# USB_Type_C.net
KiCad netlist of a schematic drawn in Altium Designer
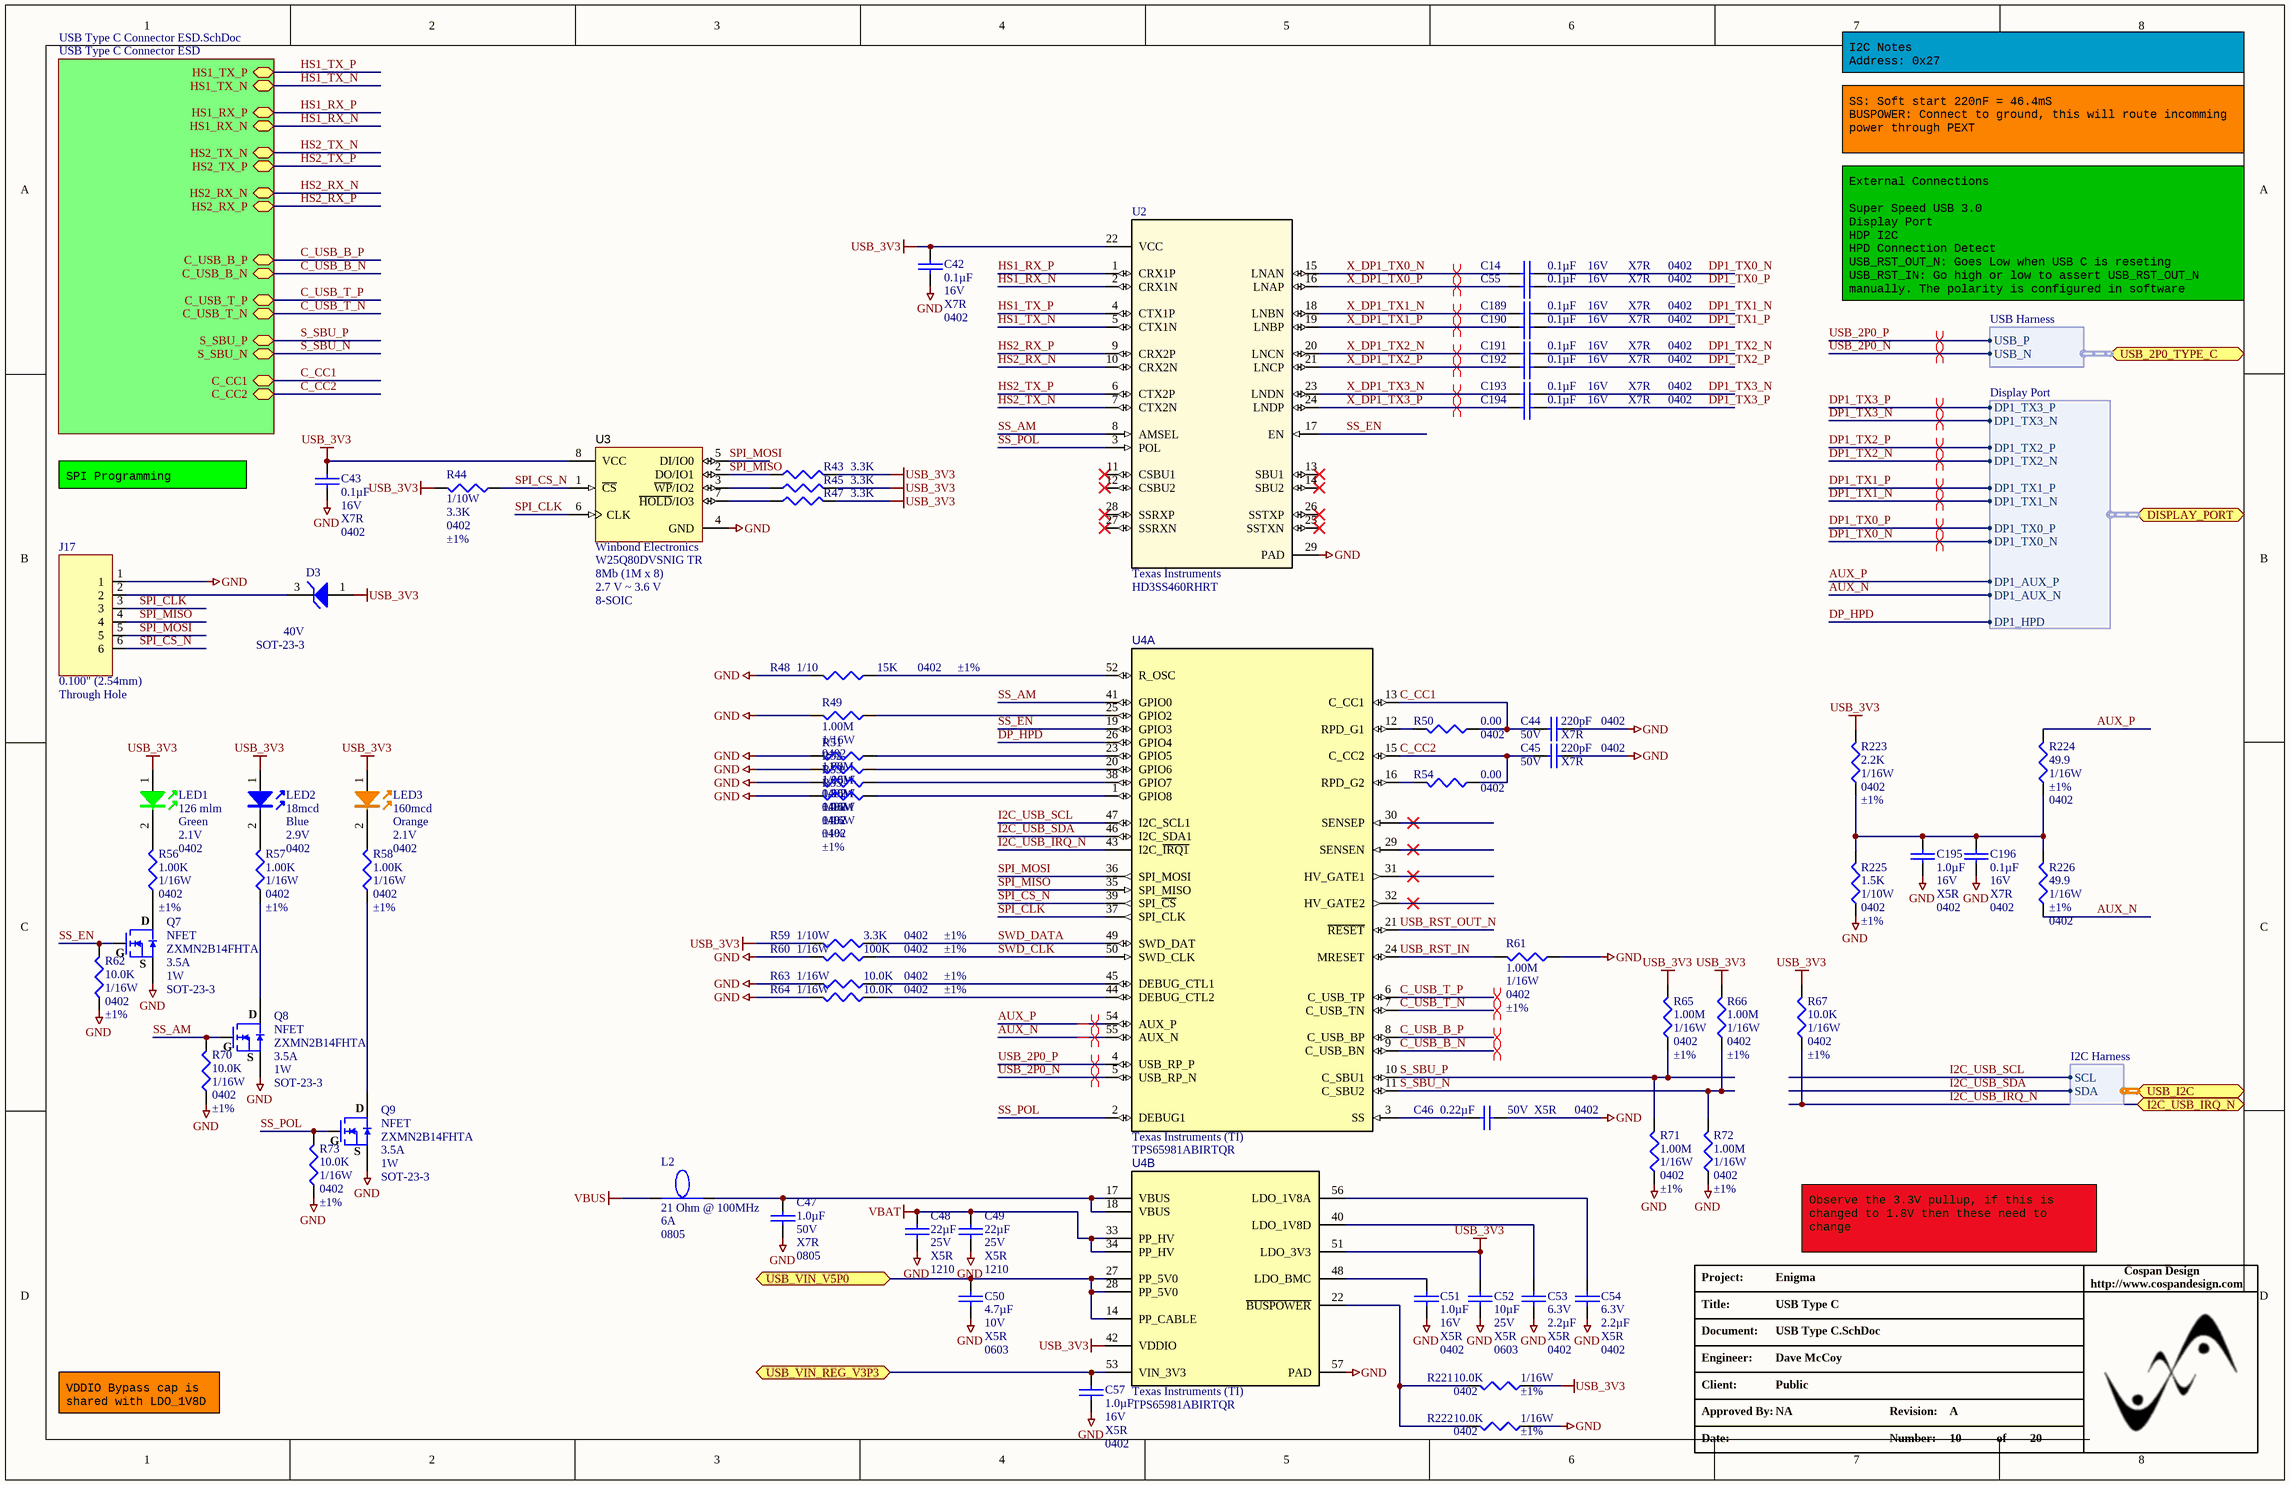
[diagram p0: USB Type C.SchDoc]

(export (version "E")
  (design (tool "Eeschema 10.0.6"))
  (components
    (comp (ref "C14")
      (value "0.1uF")
      (footprint "C_0402")
      (description "CAP CER .10UF 16V X7R 0402")
      (fields
        (field (name "MANUFACTURER") "Murata Electronics North America")
        (field (name "MANUFACTURER PART NUMBER") "GRM155R71C104KA88J")
        (field (name "CAPACITANCE") "0.1µF")
        (field (name "VOLTAGE - RATED") "16V")
        (field (name "TEMPERATURE COEFFICIENT") "X7R")
        (field (name "PACKAGE / CASE") "0402")
      )
      (libsource (lib "Main LibraryX") (part "C_0402_0.1UF_16V"))
    )
    (comp (ref "C42")
      (value "0.1uF")
      (footprint "C_0402")
      (description "CAP CER .10UF 16V X7R 0402")
      (fields
        (field (name "MANUFACTURER") "Murata Electronics North America")
        (field (name "MANUFACTURER PART NUMBER") "GRM155R71C104KA88J")
        (field (name "CAPACITANCE") "0.1µF")
        (field (name "VOLTAGE - RATED") "16V")
        (field (name "TEMPERATURE COEFFICIENT") "X7R")
        (field (name "PACKAGE / CASE") "0402")
      )
      (libsource (lib "Main LibraryX") (part "C_0402_0.1UF_16V"))
    )
    (comp (ref "C43")
      (value "0.1uF")
      (footprint "C_0402")
      (description "CAP CER .10UF 16V X7R 0402")
      (fields
        (field (name "MANUFACTURER") "Murata Electronics North America")
        (field (name "MANUFACTURER PART NUMBER") "GRM155R71C104KA88J")
        (field (name "CAPACITANCE") "0.1µF")
        (field (name "VOLTAGE - RATED") "16V")
        (field (name "TEMPERATURE COEFFICIENT") "X7R")
        (field (name "PACKAGE / CASE") "0402")
      )
      (libsource (lib "Main LibraryX") (part "C_0402_0.1UF_16V"))
    )
    (comp (ref "C44")
      (value "220pF")
      (footprint "C_0402")
      (description "CAP CER 220PF 50V 10% X7R 0402")
      (fields
        (field (name "MANUFACTURER") "Murata Electronics North America")
        (field (name "MANUFACTURER PART NUMBER") "GRM155R71H221KA01D")
        (field (name "CAPACITANCE") "220pF")
        (field (name "VOLTAGE - RATED") "50V")
        (field (name "TEMPERATURE COEFFICIENT") "X7R")
        (field (name "PACKAGE / CASE") "0402")
      )
      (libsource (lib "Main Library") (part "C_0402_220PF_50V"))
    )
    (comp (ref "C45")
      (value "220pF")
      (footprint "C_0402")
      (description "CAP CER 220PF 50V 10% X7R 0402")
      (fields
        (field (name "MANUFACTURER") "Murata Electronics North America")
        (field (name "MANUFACTURER PART NUMBER") "GRM155R71H221KA01D")
        (field (name "CAPACITANCE") "220pF")
        (field (name "VOLTAGE - RATED") "50V")
        (field (name "TEMPERATURE COEFFICIENT") "X7R")
        (field (name "PACKAGE / CASE") "0402")
      )
      (libsource (lib "Main Library") (part "C_0402_220PF_50V"))
    )
    (comp (ref "C46")
      (value "C_0402_0.22UF_50V")
      (footprint "C_0402")
      (description "CAP CER 0.22UF 50V X5R 0402")
      (fields
        (field (name "MANUFACTURER") "Taiyo Yuden")
        (field (name "MANUFACTURER PART NUMBER") "UMK105BJ224KV-F")
        (field (name "CAPACITANCE") "0.22µF")
        (field (name "VOLTAGE - RATED") "50V")
        (field (name "TEMPERATURE COEFFICIENT") "X5R")
        (field (name "PACKAGE / CASE") "0402")
      )
      (libsource (lib "Main Library") (part "C_0402_0.22UF_50V"))
    )
    (comp (ref "C47")
      (value "1.0uF")
      (footprint "C_ERA-0805")
      (description "CAP CER 1UF 50V X7R 0805")
      (fields
        (field (name "MANUFACTURER") "Murata Electronics North America")
        (field (name "MANUFACTURER PART NUMBER") "GRM21BR71H105KA12L")
        (field (name "CAPACITANCE") "1.0µF")
        (field (name "VOLTAGE - RATED") "50V")
        (field (name "TEMPERATURE COEFFICIENT") "X7R")
        (field (name "PACKAGE / CASE") "0805")
      )
      (libsource (lib "Main Library") (part "C_0805_1.0uF_50V"))
    )
    (comp (ref "C48")
      (value "22µF")
      (footprint "C_14-1210")
      (description "CAP CER 22UF 25V 20% X5R 1210")
      (fields
        (field (name "MANUFACTURER") "Taiyo Yuden")
        (field (name "MANUFACTURER PART NUMBER") "TMK325BJ226MM-T")
        (field (name "CAPACITANCE") "22µF")
        (field (name "VOLTAGE - RATED") "25V")
        (field (name "TEMPERATURE COEFFICIENT") "X5R")
        (field (name "PACKAGE / CASE") "1210")
      )
      (libsource (lib "Main Library") (part "C_1210_22µF"))
    )
    (comp (ref "C49")
      (value "22µF")
      (footprint "C_14-1210")
      (description "CAP CER 22UF 25V 20% X5R 1210")
      (fields
        (field (name "MANUFACTURER") "Taiyo Yuden")
        (field (name "MANUFACTURER PART NUMBER") "TMK325BJ226MM-T")
        (field (name "CAPACITANCE") "22µF")
        (field (name "VOLTAGE - RATED") "25V")
        (field (name "TEMPERATURE COEFFICIENT") "X5R")
        (field (name "PACKAGE / CASE") "1210")
      )
      (libsource (lib "Main Library") (part "C_1210_22µF"))
    )
    (comp (ref "C50")
      (value "4.7µF")
      (footprint "C_ERA-0603")
      (description "CAP CER 4.7UF 10V X5R 0603")
      (fields
        (field (name "MANUFACTURER") "Murata Electronics North America")
        (field (name "MANUFACTURER PART NUMBER") "GRM188R61A475KE15D")
        (field (name "CAPACITANCE") "4.7µF")
        (field (name "VOLTAGE - RATED") "10V")
        (field (name "TEMPERATURE COEFFICIENT") "X5R")
        (field (name "PACKAGE / CASE") "0603")
      )
      (libsource (lib "Main LibraryX") (part "C_0603_4.7uF_10V"))
    )
    (comp (ref "C51")
      (value "1.0uF")
      (footprint "C_ERA-0402")
      (description "CAP CER 1.0UF 16V X5R 0402")
      (fields
        (field (name "MANUFACTURER") "Taiyo Yuden")
        (field (name "MANUFACTURER PART NUMBER") "EMK105BJ105KV-F")
        (field (name "CAPACITANCE") "1.0µF")
        (field (name "VOLTAGE - RATED") "16V")
        (field (name "TEMPERATURE COEFFICIENT") "X5R")
        (field (name "PACKAGE / CASE") "0402")
      )
      (libsource (lib "Main LibraryX") (part "C_0402_1.0UF_16V"))
    )
    (comp (ref "C52")
      (value "C_0603_10µF")
      (footprint "C_ERA-0603")
      (description "CAP CER 10UF 16V X5R 0603")
      (fields
        (field (name "MANUFACTURER") "Murata Electronics North America")
        (field (name "MANUFACTURER PART NUMBER") "GRM188R61C106MA73D")
        (field (name "CAPACITANCE") "10µF")
        (field (name "VOLTAGE - RATED") "25V")
        (field (name "TEMPERATURE COEFFICIENT") "X5R")
        (field (name "PACKAGE / CASE") "0603")
      )
      (libsource (lib "Cospan Design") (part "C_0603_10µF"))
    )
    (comp (ref "C53")
      (value "2.2uF")
      (footprint "C_0402")
      (description "CAP CER 2.2UF 6.3V X5R 0402")
      (fields
        (field (name "MANUFACTURER") "TDK Corporation")
        (field (name "MANUFACTURER PART NUMBER") "C1005X5R0J225M")
        (field (name "VOLTAGE - RATED") "6.3V")
        (field (name "CAPACITANCE") "2.2µF")
        (field (name "TEMPERATURE COEFFICIENT") "X5R")
        (field (name "PACKAGE / CASE") "0402")
      )
      (libsource (lib "Main Library") (part "C_0402_2.2UF"))
    )
    (comp (ref "C54")
      (value "2.2uF")
      (footprint "C_0402")
      (description "CAP CER 2.2UF 6.3V X5R 0402")
      (fields
        (field (name "MANUFACTURER") "TDK Corporation")
        (field (name "MANUFACTURER PART NUMBER") "C1005X5R0J225M")
        (field (name "VOLTAGE - RATED") "6.3V")
        (field (name "CAPACITANCE") "2.2µF")
        (field (name "TEMPERATURE COEFFICIENT") "X5R")
        (field (name "PACKAGE / CASE") "0402")
      )
      (libsource (lib "Main Library") (part "C_0402_2.2UF"))
    )
    (comp (ref "C55")
      (value "0.1uF")
      (footprint "C_0402")
      (description "CAP CER .10UF 16V X7R 0402")
      (fields
        (field (name "MANUFACTURER") "Murata Electronics North America")
        (field (name "MANUFACTURER PART NUMBER") "GRM155R71C104KA88J")
        (field (name "CAPACITANCE") "0.1µF")
        (field (name "VOLTAGE - RATED") "16V")
        (field (name "TEMPERATURE COEFFICIENT") "X7R")
        (field (name "PACKAGE / CASE") "0402")
      )
      (libsource (lib "Main LibraryX") (part "C_0402_0.1UF_16V"))
    )
    (comp (ref "C57")
      (value "1.0uF")
      (footprint "C_ERA-0402")
      (description "CAP CER 1.0UF 16V X5R 0402")
      (fields
        (field (name "MANUFACTURER") "Taiyo Yuden")
        (field (name "MANUFACTURER PART NUMBER") "EMK105BJ105KV-F")
        (field (name "CAPACITANCE") "1.0µF")
        (field (name "VOLTAGE - RATED") "16V")
        (field (name "TEMPERATURE COEFFICIENT") "X5R")
        (field (name "PACKAGE / CASE") "0402")
      )
      (libsource (lib "Main LibraryX") (part "C_0402_1.0UF_16V"))
    )
    (comp (ref "C189")
      (value "0.1uF")
      (footprint "C_0402")
      (description "CAP CER .10UF 16V X7R 0402")
      (fields
        (field (name "MANUFACTURER") "Murata Electronics North America")
        (field (name "MANUFACTURER PART NUMBER") "GRM155R71C104KA88J")
        (field (name "CAPACITANCE") "0.1µF")
        (field (name "VOLTAGE - RATED") "16V")
        (field (name "TEMPERATURE COEFFICIENT") "X7R")
        (field (name "PACKAGE / CASE") "0402")
      )
      (libsource (lib "Main LibraryX") (part "C_0402_0.1UF_16V"))
    )
    (comp (ref "C190")
      (value "0.1uF")
      (footprint "C_0402")
      (description "CAP CER .10UF 16V X7R 0402")
      (fields
        (field (name "MANUFACTURER") "Murata Electronics North America")
        (field (name "MANUFACTURER PART NUMBER") "GRM155R71C104KA88J")
        (field (name "CAPACITANCE") "0.1µF")
        (field (name "VOLTAGE - RATED") "16V")
        (field (name "TEMPERATURE COEFFICIENT") "X7R")
        (field (name "PACKAGE / CASE") "0402")
      )
      (libsource (lib "Main LibraryX") (part "C_0402_0.1UF_16V"))
    )
    (comp (ref "C191")
      (value "0.1uF")
      (footprint "C_0402")
      (description "CAP CER .10UF 16V X7R 0402")
      (fields
        (field (name "MANUFACTURER") "Murata Electronics North America")
        (field (name "MANUFACTURER PART NUMBER") "GRM155R71C104KA88J")
        (field (name "CAPACITANCE") "0.1µF")
        (field (name "VOLTAGE - RATED") "16V")
        (field (name "TEMPERATURE COEFFICIENT") "X7R")
        (field (name "PACKAGE / CASE") "0402")
      )
      (libsource (lib "Main LibraryX") (part "C_0402_0.1UF_16V"))
    )
    (comp (ref "C192")
      (value "0.1uF")
      (footprint "C_0402")
      (description "CAP CER .10UF 16V X7R 0402")
      (fields
        (field (name "MANUFACTURER") "Murata Electronics North America")
        (field (name "MANUFACTURER PART NUMBER") "GRM155R71C104KA88J")
        (field (name "CAPACITANCE") "0.1µF")
        (field (name "VOLTAGE - RATED") "16V")
        (field (name "TEMPERATURE COEFFICIENT") "X7R")
        (field (name "PACKAGE / CASE") "0402")
      )
      (libsource (lib "Main LibraryX") (part "C_0402_0.1UF_16V"))
    )
    (comp (ref "C193")
      (value "0.1uF")
      (footprint "C_0402")
      (description "CAP CER .10UF 16V X7R 0402")
      (fields
        (field (name "MANUFACTURER") "Murata Electronics North America")
        (field (name "MANUFACTURER PART NUMBER") "GRM155R71C104KA88J")
        (field (name "CAPACITANCE") "0.1µF")
        (field (name "VOLTAGE - RATED") "16V")
        (field (name "TEMPERATURE COEFFICIENT") "X7R")
        (field (name "PACKAGE / CASE") "0402")
      )
      (libsource (lib "Main LibraryX") (part "C_0402_0.1UF_16V"))
    )
    (comp (ref "C194")
      (value "0.1uF")
      (footprint "C_0402")
      (description "CAP CER .10UF 16V X7R 0402")
      (fields
        (field (name "MANUFACTURER") "Murata Electronics North America")
        (field (name "MANUFACTURER PART NUMBER") "GRM155R71C104KA88J")
        (field (name "CAPACITANCE") "0.1µF")
        (field (name "VOLTAGE - RATED") "16V")
        (field (name "TEMPERATURE COEFFICIENT") "X7R")
        (field (name "PACKAGE / CASE") "0402")
      )
      (libsource (lib "Main LibraryX") (part "C_0402_0.1UF_16V"))
    )
    (comp (ref "C195")
      (value "1.0uF")
      (footprint "C_ERA-0402")
      (description "CAP CER 1.0UF 16V X5R 0402")
      (fields
        (field (name "MANUFACTURER") "Taiyo Yuden")
        (field (name "MANUFACTURER PART NUMBER") "EMK105BJ105KV-F")
        (field (name "CAPACITANCE") "1.0µF")
        (field (name "VOLTAGE - RATED") "16V")
        (field (name "TEMPERATURE COEFFICIENT") "X5R")
        (field (name "PACKAGE / CASE") "0402")
      )
      (libsource (lib "Main LibraryX") (part "C_0402_1.0UF_16V"))
    )
    (comp (ref "C196")
      (value "0.1uF")
      (footprint "C_0402")
      (description "CAP CER .10UF 16V X7R 0402")
      (fields
        (field (name "MANUFACTURER") "Murata Electronics North America")
        (field (name "MANUFACTURER PART NUMBER") "GRM155R71C104KA88J")
        (field (name "CAPACITANCE") "0.1µF")
        (field (name "VOLTAGE - RATED") "16V")
        (field (name "TEMPERATURE COEFFICIENT") "X7R")
        (field (name "PACKAGE / CASE") "0402")
      )
      (libsource (lib "Main LibraryX") (part "C_0402_0.1UF_16V"))
    )
    (comp (ref "D3")
      (value "BZX84C16-7-F")
      (footprint "SOT23")
      (description "DIODE SCHOTTKY 40V 500MA SOT23-3")
      (fields
        (field (name "MANUFACTURER") "Diodes Incorporated")
        (field (name "MANUFACTURER PART NUMBER") "BAT400D-7-F")
        (field (name "VOLTAGE - ZENER (NOM) (VZ)") "40V")
        (field (name "SUPPLIER DEVICE PACKAGE") "SOT-23-3")
      )
      (libsource (lib "Cospan Design") (part "D_SCHOTTKY_40V_SOT23"))
    )
    (comp (ref "J17")
      (value "J_HDR1X6_THRHOLE_VERT")
      (footprint "HDR_1X6")
      (description "CONN HEADER .100\" 12POS TIN PCB")
      (fields
        (field (name "MANUFACTURER") "Samtec")
        (field (name "MANUFACTURER PART NUMBER") "TSW-106-07-T-S")
        (field (name "PITCH") "0.100\" (2.54mm)")
        (field (name "MOUNTING TYPE") "Through Hole")
      )
      (libsource (lib "Main Library") (part "J_HDR1X6_THRHOLE_VERT"))
    )
    (comp (ref "L2")
      (value "L_FB_21OHM_100MHZ")
      (footprint "C_ERA-0805")
      (description "FERRITE BEAD 21 OHM 0805 1LN")
      (fields
        (field (name "MANUFACTURER") "Taiyo Yuden")
        (field (name "MANUFACTURER PART NUMBER") "FBMJ2125HM210NT")
        (field (name "IMPEDANCE @ FREQUENCY") "21 Ohm @ 100MHz")
        (field (name "CURRENT RATING") "6A")
        (field (name "PACKAGE / CASE") "0805")
      )
      (libsource (lib "Main LibraryX") (part "L_FB_21OHM_100MHZ"))
    )
    (comp (ref "LED1")
      (value "LED_GRN_0402")
      (footprint "DIOM1005X07L_GREEN")
      (description "LED 1X0.5MM 570NM GN WTR CLR SMD")
      (fields
        (field (name "MANUFACTURER") "Kingbright Corp")
        (field (name "MANUFACTURER PART NUMBER") "APHHS1005CGCK")
        (field (name "LUMINOUS FLUX @ CURRENT - TEST") "126 mlm")
        (field (name "COLOR") "Green")
        (field (name "VOLTAGE - FORWARD (VF) TYP") "2.1V")
        (field (name "PACKAGE / CASE") "0402")
      )
      (libsource (lib "Main Library") (part "LED_GRN_0402"))
    )
    (comp (ref "LED2")
      (value "LED_BLUE_0402")
      (footprint "DIOM1005X07L_BLUE")
      (description "LED 1X0.5MM 470NM BL WTR CLR SMD")
      (fields
        (field (name "MANUFACTURER") "Panasonic Electronic Components - Semiconductor Products")
        (field (name "MANUFACTURER PART NUMBER") "LNJ947W8CRA")
        (field (name "LUMINOUS FLUX @ CURRENT - TEST") "18mcd")
        (field (name "COLOR") "Blue")
        (field (name "VOLTAGE - FORWARD (VF) TYP") "2.9V")
        (field (name "PACKAGE / CASE") "0402")
      )
      (libsource (lib "Main Library") (part "LED_BLUE_0402"))
    )
    (comp (ref "LED3")
      (value "LED_ORN_0402")
      (footprint "DIOM1005X07L_ORANGE")
      (description "LED 1X0.5MM 601NM ORN WTRCLR SMD")
      (fields
        (field (name "MANUFACTURER") "Kingbright Corp")
        (field (name "MANUFACTURER PART NUMBER") "APHHS1005SECK")
        (field (name "MILLICANDELA RATING") "160mcd")
        (field (name "COLOR") "Orange")
        (field (name "VOLTAGE - FORWARD (VF) TYP") "2.1V")
        (field (name "PACKAGE / CASE") "0402")
      )
      (libsource (lib "Main Library") (part "LED_ORN_0402"))
    )
    (comp (ref "Q7")
      (value "NFET")
      (footprint "SOT-23A")
      (description "MOSFET N-CH 20V 3.5A SOT23-3")
      (fields
        (field (name "MANUFACTURER") "Diodes Incorporated")
        (field (name "MANUFACTURER PART NUMBER") "ZXMN2B14FHTA")
        (field (name "CURRENT - CONTINUOUS DRAIN (ID) @ 25° C") "3.5A")
        (field (name "POWER - MAX") "1W")
        (field (name "PACKAGE / CASE") "SOT-23-3")
      )
      (libsource (lib "Main LibraryX") (part "Q_NFET_3.50A_SOT23"))
    )
    (comp (ref "Q8")
      (value "NFET")
      (footprint "SOT-23A")
      (description "MOSFET N-CH 20V 3.5A SOT23-3")
      (fields
        (field (name "MANUFACTURER") "Diodes Incorporated")
        (field (name "MANUFACTURER PART NUMBER") "ZXMN2B14FHTA")
        (field (name "CURRENT - CONTINUOUS DRAIN (ID) @ 25° C") "3.5A")
        (field (name "POWER - MAX") "1W")
        (field (name "PACKAGE / CASE") "SOT-23-3")
      )
      (libsource (lib "Main LibraryX") (part "Q_NFET_3.50A_SOT23"))
    )
    (comp (ref "Q9")
      (value "NFET")
      (footprint "SOT-23A")
      (description "MOSFET N-CH 20V 3.5A SOT23-3")
      (fields
        (field (name "MANUFACTURER") "Diodes Incorporated")
        (field (name "MANUFACTURER PART NUMBER") "ZXMN2B14FHTA")
        (field (name "CURRENT - CONTINUOUS DRAIN (ID) @ 25° C") "3.5A")
        (field (name "POWER - MAX") "1W")
        (field (name "PACKAGE / CASE") "SOT-23-3")
      )
      (libsource (lib "Main LibraryX") (part "Q_NFET_3.50A_SOT23"))
    )
    (comp (ref "R43")
      (value "3.3k Ohms")
      (footprint "R_0402")
      (description "RES 3.30K OHM 1/10W 1% 0402 SM")
      (fields
        (field (name "MANUFACTURER") "Panasonic - ECG")
        (field (name "MANUFACTURER PART NUMBER") "ERJ-2RKF3301X")
        (field (name "RESISTANCE IN OHMS") "3.3K")
      )
      (libsource (lib "Main Library") (part "R_0402_3.3K"))
    )
    (comp (ref "R44")
      (value "3.3k Ohms")
      (footprint "R_0402")
      (description "RES 3.30K OHM 1/10W 1% 0402 SM")
      (fields
        (field (name "MANUFACTURER") "Panasonic - ECG")
        (field (name "MANUFACTURER PART NUMBER") "ERJ-2RKF3301X")
        (field (name "POWER (WATTS)") "1/10W")
        (field (name "RESISTANCE IN OHMS") "3.3K")
        (field (name "CASE") "0402")
        (field (name "TOLERANCE") "±1%")
      )
      (libsource (lib "Main Library") (part "R_0402_3.3K"))
    )
    (comp (ref "R45")
      (value "3.3k Ohms")
      (footprint "R_0402")
      (description "RES 3.30K OHM 1/10W 1% 0402 SM")
      (fields
        (field (name "MANUFACTURER") "Panasonic - ECG")
        (field (name "MANUFACTURER PART NUMBER") "ERJ-2RKF3301X")
        (field (name "RESISTANCE IN OHMS") "3.3K")
      )
      (libsource (lib "Main Library") (part "R_0402_3.3K"))
    )
    (comp (ref "R47")
      (value "3.3k Ohms")
      (footprint "R_0402")
      (description "RES 3.30K OHM 1/10W 1% 0402 SM")
      (fields
        (field (name "MANUFACTURER") "Panasonic - ECG")
        (field (name "MANUFACTURER PART NUMBER") "ERJ-2RKF3301X")
        (field (name "RESISTANCE IN OHMS") "3.3K")
      )
      (libsource (lib "Main Library") (part "R_0402_3.3K"))
    )
    (comp (ref "R48")
      (value "R_0402_15.0K")
      (footprint "R_0402")
      (description "RES 15.0K OHM 1/10W 1% 0402 SMD")
      (fields
        (field (name "MANUFACTURER") "Panasonic - ECG")
        (field (name "MANUFACTURER PART NUMBER") "ERJ-2RKF1502X")
        (field (name "RESISTANCE IN OHMS") "15K")
        (field (name "POWER (WATTS)") "1/10")
        (field (name "CASE") "0402")
        (field (name "TOLERANCE") "±1%")
      )
      (libsource (lib "Main Library") (part "R_0402_15.0K"))
    )
    (comp (ref "R49")
      (value "1.0M Ohms")
      (footprint "R_0402")
      (description "RES 1.00M OHM 1/16W 1% 0402 SMD")
      (fields
        (field (name "MANUFACTURER") "Yageo")
        (field (name "MANUFACTURER PART NUMBER") "RC0402FR-071ML")
        (field (name "RESISTANCE IN OHMS") "1.00M")
        (field (name "POWER (WATTS)") "1/16W")
        (field (name "CASE") "0402")
        (field (name "TOLERANCE") "±1%")
      )
      (libsource (lib "Main LibraryX") (part "R_0402_1.0M"))
    )
    (comp (ref "R50")
      (value "0.0 Ohms")
      (footprint "R_0402")
      (description "RES SMD 0.0OHM JUMPER 1/10W 0402")
      (fields
        (field (name "MANUFACTURER") "Panasonic - ECG")
        (field (name "MANUFACTURER PART NUMBER") "ERJ-2GE0R00X")
        (field (name "RESISTANCE IN OHMS") "0.00")
        (field (name "CASE") "0402")
      )
      (libsource (lib "Main Library") (part "R_0402_0.00"))
    )
    (comp (ref "R51")
      (value "1.0M Ohms")
      (footprint "R_0402")
      (description "RES 1.00M OHM 1/16W 1% 0402 SMD")
      (fields
        (field (name "MANUFACTURER") "Yageo")
        (field (name "MANUFACTURER PART NUMBER") "RC0402FR-071ML")
        (field (name "RESISTANCE IN OHMS") "1.00M")
        (field (name "POWER (WATTS)") "1/16W")
        (field (name "CASE") "0402")
        (field (name "TOLERANCE") "±1%")
      )
      (libsource (lib "Main LibraryX") (part "R_0402_1.0M"))
    )
    (comp (ref "R52")
      (value "1.0M Ohms")
      (footprint "R_0402")
      (description "RES 1.00M OHM 1/16W 1% 0402 SMD")
      (fields
        (field (name "MANUFACTURER") "Yageo")
        (field (name "MANUFACTURER PART NUMBER") "RC0402FR-071ML")
        (field (name "RESISTANCE IN OHMS") "1.00M")
        (field (name "POWER (WATTS)") "1/16W")
        (field (name "CASE") "0402")
        (field (name "TOLERANCE") "±1%")
      )
      (libsource (lib "Main LibraryX") (part "R_0402_1.0M"))
    )
    (comp (ref "R53")
      (value "1.0M Ohms")
      (footprint "R_0402")
      (description "RES 1.00M OHM 1/16W 1% 0402 SMD")
      (fields
        (field (name "MANUFACTURER") "Yageo")
        (field (name "MANUFACTURER PART NUMBER") "RC0402FR-071ML")
        (field (name "RESISTANCE IN OHMS") "1.00M")
        (field (name "POWER (WATTS)") "1/16W")
        (field (name "CASE") "0402")
        (field (name "TOLERANCE") "±1%")
      )
      (libsource (lib "Main LibraryX") (part "R_0402_1.0M"))
    )
    (comp (ref "R54")
      (value "0.0 Ohms")
      (footprint "R_0402")
      (description "RES SMD 0.0OHM JUMPER 1/10W 0402")
      (fields
        (field (name "MANUFACTURER") "Panasonic - ECG")
        (field (name "MANUFACTURER PART NUMBER") "ERJ-2GE0R00X")
        (field (name "RESISTANCE IN OHMS") "0.00")
        (field (name "CASE") "0402")
      )
      (libsource (lib "Main Library") (part "R_0402_0.00"))
    )
    (comp (ref "R55")
      (value "1.0M Ohms")
      (footprint "R_0402")
      (description "RES 1.00M OHM 1/16W 1% 0402 SMD")
      (fields
        (field (name "MANUFACTURER") "Yageo")
        (field (name "MANUFACTURER PART NUMBER") "RC0402FR-071ML")
        (field (name "RESISTANCE IN OHMS") "1.00M")
        (field (name "POWER (WATTS)") "1/16W")
        (field (name "CASE") "0402")
        (field (name "TOLERANCE") "±1%")
      )
      (libsource (lib "Main LibraryX") (part "R_0402_1.0M"))
    )
    (comp (ref "R56")
      (value "1.0k Ohms")
      (footprint "R_0402")
      (description "RES 1.00K OHM 1/16W 1% 0402 SMD")
      (fields
        (field (name "MANUFACTURER") "Yageo")
        (field (name "MANUFACTURER PART NUMBER") "RC0402FR-071KL")
        (field (name "RESISTANCE IN OHMS") "1.00K")
        (field (name "POWER (WATTS)") "1/16W")
        (field (name "CASE") "0402")
        (field (name "TOLERANCE") "±1%")
      )
      (libsource (lib "Main Library") (part "R_0402_1.0K"))
    )
    (comp (ref "R57")
      (value "1.0k Ohms")
      (footprint "R_0402")
      (description "RES 1.00K OHM 1/16W 1% 0402 SMD")
      (fields
        (field (name "MANUFACTURER") "Yageo")
        (field (name "MANUFACTURER PART NUMBER") "RC0402FR-071KL")
        (field (name "RESISTANCE IN OHMS") "1.00K")
        (field (name "POWER (WATTS)") "1/16W")
        (field (name "CASE") "0402")
        (field (name "TOLERANCE") "±1%")
      )
      (libsource (lib "Main Library") (part "R_0402_1.0K"))
    )
    (comp (ref "R58")
      (value "1.0k Ohms")
      (footprint "R_0402")
      (description "RES 1.00K OHM 1/16W 1% 0402 SMD")
      (fields
        (field (name "MANUFACTURER") "Yageo")
        (field (name "MANUFACTURER PART NUMBER") "RC0402FR-071KL")
        (field (name "RESISTANCE IN OHMS") "1.00K")
        (field (name "POWER (WATTS)") "1/16W")
        (field (name "CASE") "0402")
        (field (name "TOLERANCE") "±1%")
      )
      (libsource (lib "Main Library") (part "R_0402_1.0K"))
    )
    (comp (ref "R59")
      (value "3.3k Ohms")
      (footprint "R_0402")
      (description "RES 3.30K OHM 1/10W 1% 0402 SM")
      (fields
        (field (name "MANUFACTURER") "Panasonic - ECG")
        (field (name "MANUFACTURER PART NUMBER") "ERJ-2RKF3301X")
        (field (name "POWER (WATTS)") "1/10W")
        (field (name "RESISTANCE IN OHMS") "3.3K")
        (field (name "CASE") "0402")
        (field (name "TOLERANCE") "±1%")
      )
      (libsource (lib "Main Library") (part "R_0402_3.3K"))
    )
    (comp (ref "R60")
      (value "R_0402_100K")
      (footprint "R_0402")
      (description "RES SMD 100K OHM 1% 1/16W 0402")
      (fields
        (field (name "MANUFACTURER") "Yageo")
        (field (name "MANUFACTURER PART NUMBER") "RC0402FR-07100KL")
        (field (name "RESISTANCE IN OHMS") "100K")
        (field (name "POWER (WATTS)") "1/16W")
        (field (name "CASE") "0402")
        (field (name "TOLERANCE") "±1%")
      )
      (libsource (lib "Cospan Design") (part "R_0402_100K"))
    )
    (comp (ref "R61")
      (value "1.0M Ohms")
      (footprint "R_0402")
      (description "RES 1.00M OHM 1/16W 1% 0402 SMD")
      (fields
        (field (name "MANUFACTURER") "Yageo")
        (field (name "MANUFACTURER PART NUMBER") "RC0402FR-071ML")
        (field (name "RESISTANCE IN OHMS") "1.00M")
        (field (name "POWER (WATTS)") "1/16W")
        (field (name "CASE") "0402")
        (field (name "TOLERANCE") "±1%")
      )
      (libsource (lib "Main LibraryX") (part "R_0402_1.0M"))
    )
    (comp (ref "R62")
      (value "R_0402_10.0K")
      (footprint "R_0402")
      (description "RES 10.0K OHM 1/16W 1% 0402 SMD")
      (fields
        (field (name "MANUFACTURER") "Stackpole Electronics Inc")
        (field (name "MANUFACTURER PART NUMBER") "RMCF0402FT10K0")
        (field (name "RESISTANCE IN OHMS") "10.0K")
        (field (name "POWER (WATTS)") "1/16W")
        (field (name "CASE") "0402")
        (field (name "TOLERANCE") "±1%")
      )
      (libsource (lib "Main Library") (part "R_0402_10.0K"))
    )
    (comp (ref "R63")
      (value "R_0402_10.0K")
      (footprint "R_0402")
      (description "RES 10.0K OHM 1/16W 1% 0402 SMD")
      (fields
        (field (name "MANUFACTURER") "Stackpole Electronics Inc")
        (field (name "MANUFACTURER PART NUMBER") "RMCF0402FT10K0")
        (field (name "RESISTANCE IN OHMS") "10.0K")
        (field (name "POWER (WATTS)") "1/16W")
        (field (name "CASE") "0402")
        (field (name "TOLERANCE") "±1%")
      )
      (libsource (lib "Cospan Design") (part "R_0402_10.0K"))
    )
    (comp (ref "R64")
      (value "R_0402_10.0K")
      (footprint "R_0402")
      (description "RES 10.0K OHM 1/16W 1% 0402 SMD")
      (fields
        (field (name "MANUFACTURER") "Stackpole Electronics Inc")
        (field (name "MANUFACTURER PART NUMBER") "RMCF0402FT10K0")
        (field (name "RESISTANCE IN OHMS") "10.0K")
        (field (name "POWER (WATTS)") "1/16W")
        (field (name "CASE") "0402")
        (field (name "TOLERANCE") "±1%")
      )
      (libsource (lib "Cospan Design") (part "R_0402_10.0K"))
    )
    (comp (ref "R65")
      (value "1.0M Ohms")
      (footprint "R_0402")
      (description "RES 1.00M OHM 1/16W 1% 0402 SMD")
      (fields
        (field (name "MANUFACTURER") "Yageo")
        (field (name "MANUFACTURER PART NUMBER") "RC0402FR-071ML")
        (field (name "RESISTANCE IN OHMS") "1.00M")
        (field (name "POWER (WATTS)") "1/16W")
        (field (name "CASE") "0402")
        (field (name "TOLERANCE") "±1%")
      )
      (libsource (lib "Main LibraryX") (part "R_0402_1.0M"))
    )
    (comp (ref "R66")
      (value "1.0M Ohms")
      (footprint "R_0402")
      (description "RES 1.00M OHM 1/16W 1% 0402 SMD")
      (fields
        (field (name "MANUFACTURER") "Yageo")
        (field (name "MANUFACTURER PART NUMBER") "RC0402FR-071ML")
        (field (name "RESISTANCE IN OHMS") "1.00M")
        (field (name "POWER (WATTS)") "1/16W")
        (field (name "CASE") "0402")
        (field (name "TOLERANCE") "±1%")
      )
      (libsource (lib "Main LibraryX") (part "R_0402_1.0M"))
    )
    (comp (ref "R67")
      (value "R_0402_10.0K")
      (footprint "R_0402")
      (description "RES 10.0K OHM 1/16W 1% 0402 SMD")
      (fields
        (field (name "MANUFACTURER") "Stackpole Electronics Inc")
        (field (name "MANUFACTURER PART NUMBER") "RMCF0402FT10K0")
        (field (name "RESISTANCE IN OHMS") "10.0K")
        (field (name "POWER (WATTS)") "1/16W")
        (field (name "CASE") "0402")
        (field (name "TOLERANCE") "±1%")
      )
      (libsource (lib "Cospan Design") (part "R_0402_10.0K"))
    )
    (comp (ref "R70")
      (value "R_0402_10.0K")
      (footprint "R_0402")
      (description "RES 10.0K OHM 1/16W 1% 0402 SMD")
      (fields
        (field (name "MANUFACTURER") "Stackpole Electronics Inc")
        (field (name "MANUFACTURER PART NUMBER") "RMCF0402FT10K0")
        (field (name "RESISTANCE IN OHMS") "10.0K")
        (field (name "POWER (WATTS)") "1/16W")
        (field (name "CASE") "0402")
        (field (name "TOLERANCE") "±1%")
      )
      (libsource (lib "Main Library") (part "R_0402_10.0K"))
    )
    (comp (ref "R71")
      (value "1.0M Ohms")
      (footprint "R_0402")
      (description "RES 1.00M OHM 1/16W 1% 0402 SMD")
      (fields
        (field (name "MANUFACTURER") "Yageo")
        (field (name "MANUFACTURER PART NUMBER") "RC0402FR-071ML")
        (field (name "RESISTANCE IN OHMS") "1.00M")
        (field (name "POWER (WATTS)") "1/16W")
        (field (name "CASE") "0402")
        (field (name "TOLERANCE") "±1%")
      )
      (libsource (lib "Main LibraryX") (part "R_0402_1.0M"))
    )
    (comp (ref "R72")
      (value "1.0M Ohms")
      (footprint "R_0402")
      (description "RES 1.00M OHM 1/16W 1% 0402 SMD")
      (fields
        (field (name "MANUFACTURER") "Yageo")
        (field (name "MANUFACTURER PART NUMBER") "RC0402FR-071ML")
        (field (name "RESISTANCE IN OHMS") "1.00M")
        (field (name "POWER (WATTS)") "1/16W")
        (field (name "CASE") "0402")
        (field (name "TOLERANCE") "±1%")
      )
      (libsource (lib "Main LibraryX") (part "R_0402_1.0M"))
    )
    (comp (ref "R73")
      (value "R_0402_10.0K")
      (footprint "R_0402")
      (description "RES 10.0K OHM 1/16W 1% 0402 SMD")
      (fields
        (field (name "MANUFACTURER") "Stackpole Electronics Inc")
        (field (name "MANUFACTURER PART NUMBER") "RMCF0402FT10K0")
        (field (name "RESISTANCE IN OHMS") "10.0K")
        (field (name "POWER (WATTS)") "1/16W")
        (field (name "CASE") "0402")
        (field (name "TOLERANCE") "±1%")
      )
      (libsource (lib "Main Library") (part "R_0402_10.0K"))
    )
    (comp (ref "R221")
      (value "R_0402_10.0K")
      (footprint "R_0402")
      (description "RES 10.0K OHM 1/16W 1% 0402 SMD")
      (fields
        (field (name "MANUFACTURER") "Stackpole Electronics Inc")
        (field (name "MANUFACTURER PART NUMBER") "RMCF0402FT10K0")
        (field (name "RESISTANCE IN OHMS") "10.0K")
        (field (name "POWER (WATTS)") "1/16W")
        (field (name "CASE") "0402")
        (field (name "TOLERANCE") "±1%")
      )
      (libsource (lib "Cospan Design") (part "R_0402_10.0K"))
    )
    (comp (ref "R222")
      (value "R_0402_10.0K")
      (footprint "R_0402")
      (description "RES 10.0K OHM 1/16W 1% 0402 SMD")
      (fields
        (field (name "MANUFACTURER") "Stackpole Electronics Inc")
        (field (name "MANUFACTURER PART NUMBER") "RMCF0402FT10K0")
        (field (name "RESISTANCE IN OHMS") "10.0K")
        (field (name "POWER (WATTS)") "1/16W")
        (field (name "CASE") "0402")
        (field (name "TOLERANCE") "±1%")
      )
      (libsource (lib "Cospan Design") (part "R_0402_10.0K"))
    )
    (comp (ref "R223")
      (value "R_0402_2.2K")
      (footprint "R_0402")
      (description "RES SMD 2.2K OHM 1% 1/10W 0402")
      (fields
        (field (name "MANUFACTURER") "Panasonic Electronic Components")
        (field (name "MANUFACTURER PART NUMBER") "ERJ-2RKF2201X")
        (field (name "RESISTANCE IN OHMS") "2.2K")
        (field (name "POWER (WATTS)") "1/16W")
        (field (name "CASE") "0402")
        (field (name "TOLERANCE") "±1%")
      )
      (libsource (lib "Cospan Design") (part "R_0402_2.2K"))
    )
    (comp (ref "R224")
      (value "R_0402_49.9")
      (footprint "R_0402")
      (description "RES 49.9 OHM 1/16W 1% 0402 SMD")
      (fields
        (field (name "MANUFACTURER") "Stackpole Electronics Inc")
        (field (name "MANUFACTURER PART NUMBER") "RMCF0402FT49R9")
        (field (name "RESISTANCE (OHMS)") "49.9")
        (field (name "POWER (WATTS)") "1/16W")
        (field (name "TOLERANCE") "±1%")
        (field (name "PACKAGE / CASE") "0402")
      )
      (libsource (lib "Main Library") (part "R_0402_49.9"))
    )
    (comp (ref "R225")
      (value "1.5k Ohms")
      (footprint "R_0402")
      (description "RES 1.50K OHM 1/10W 1% 0402 SMD")
      (fields
        (field (name "MANUFACTURER") "Panasonic - ECG")
        (field (name "MANUFACTURER PART NUMBER") "ERJ-2RKF1501X")
        (field (name "RESISTANCE IN OHMS") "1.5K")
        (field (name "POWER (WATTS)") "1/10W")
        (field (name "CASE") "0402")
        (field (name "TOLERANCE") "±1%")
      )
      (libsource (lib "Main Library") (part "R_0402_1.5K"))
    )
    (comp (ref "R226")
      (value "R_0402_49.9")
      (footprint "R_0402")
      (description "RES 49.9 OHM 1/16W 1% 0402 SMD")
      (fields
        (field (name "MANUFACTURER") "Stackpole Electronics Inc")
        (field (name "MANUFACTURER PART NUMBER") "RMCF0402FT49R9")
        (field (name "RESISTANCE (OHMS)") "49.9")
        (field (name "POWER (WATTS)") "1/16W")
        (field (name "TOLERANCE") "±1%")
        (field (name "PACKAGE / CASE") "0402")
      )
      (libsource (lib "Main Library") (part "R_0402_49.9"))
    )
    (comp (ref "U2")
      (value "U_HD3SS460RHRR")
      (footprint "RHR0028A")
      (description "IC MUX/DEMUX 4CH TYPE C2 28WQFN")
      (fields
        (field (name "PARTNUMBER") "HD3SS460RHRR")
        (field (name "ALTERNATE PARTNUMBER") "HD3SS460RHRT")
        (field (name "MANUFACTURER") "Texas Instruments")
        (field (name "MANUFACTURER PART NUMBER") "HD3SS460RHRT")
      )
      (libsource (lib "Cospan Design") (part "U_HD3SS460RHRR"))
    )
    (comp (ref "U3")
      (value "U_W25Q80DVSNIG")
      (footprint "SOIC-8 - TI")
      (description "IC FLASH 8MBIT 104MHZ 8SOIC")
      (fields
        (field (name "MANUFACTURER") "Winbond Electronics")
        (field (name "MANUFACTURER PART NUMBER") "W25Q80DVSNIG TR")
        (field (name "MEMORY SIZE") "8Mb (1M x 8)")
        (field (name "VOLTAGE - SUPPLY") "2.7 V ~ 3.6 V")
        (field (name "SUPPLIER DEVICE PACKAGE") "8-SOIC")
      )
      (libsource (lib "Cospan Design") (part "U_W25Q80DVSNIG"))
    )
    (comp (ref "U4")
      (value "~")
      (footprint "RWE0056B")
      (description "USB, Type-C Controller PMIC 56-QFN (8x8)")
      (fields
        (field (name "MANUFACTURER") "Texas Instruments (TI)")
        (field (name "MANUFACTURER PART NUMBER") "TPS65981ABIRTQR")
      )
      (libsource (lib "Cospan Design") (part "U_TPS65981ABQWRWERQ1"))
    )
  )
  (nets
    (net (code "6") (name "/AUX_N") (class "Default")
      (node (ref "R226") (pin "2") (pinfunction "2_2") (pintype "passive"))
      (node (ref "U4") (pin "55") (pinfunction "AUX_N_55") (pintype "bidirectional"))
    )
    (net (code "7") (name "/AUX_P") (class "Default")
      (node (ref "R224") (pin "1") (pinfunction "1_1") (pintype "passive"))
      (node (ref "U4") (pin "54") (pinfunction "AUX_P_54") (pintype "bidirectional"))
    )
    (net (code "8") (name "/C_CC1") (class "Default")
      (node (ref "C44") (pin "2") (pinfunction "2_2") (pintype "passive"))
      (node (ref "R50") (pin "2") (pinfunction "2_2") (pintype "passive"))
      (node (ref "U4") (pin "13") (pinfunction "C_CC1_13") (pintype "bidirectional"))
    )
    (net (code "9") (name "/C_CC2") (class "Default")
      (node (ref "C45") (pin "2") (pinfunction "2_2") (pintype "passive"))
      (node (ref "R54") (pin "2") (pinfunction "2_2") (pintype "passive"))
      (node (ref "U4") (pin "15") (pinfunction "C_CC2_15") (pintype "bidirectional"))
    )
    (net (code "10") (name "/C_USB_B_N") (class "Default")
      (node (ref "U4") (pin "9") (pinfunction "C_USB_BN_9") (pintype "bidirectional"))
    )
    (net (code "11") (name "/C_USB_B_P") (class "Default")
      (node (ref "U4") (pin "8") (pinfunction "C_USB_BP_8") (pintype "bidirectional"))
    )
    (net (code "12") (name "/C_USB_T_N") (class "Default")
      (node (ref "U4") (pin "7") (pinfunction "C_USB_TN_7") (pintype "bidirectional"))
    )
    (net (code "13") (name "/C_USB_T_P") (class "Default")
      (node (ref "U4") (pin "6") (pinfunction "C_USB_TP_6") (pintype "bidirectional"))
    )
    (net (code "14") (name "/DP1_TX0_N") (class "Default")
      (node (ref "C14") (pin "1") (pinfunction "1_1") (pintype "passive"))
    )
    (net (code "15") (name "/DP1_TX0_P") (class "Default")
      (node (ref "C55") (pin "1") (pinfunction "1_1") (pintype "passive"))
    )
    (net (code "16") (name "/DP1_TX1_N") (class "Default")
      (node (ref "C189") (pin "1") (pinfunction "1_1") (pintype "passive"))
    )
    (net (code "17") (name "/DP1_TX1_P") (class "Default")
      (node (ref "C190") (pin "1") (pinfunction "1_1") (pintype "passive"))
    )
    (net (code "18") (name "/DP1_TX2_N") (class "Default")
      (node (ref "C191") (pin "1") (pinfunction "1_1") (pintype "passive"))
    )
    (net (code "19") (name "/DP1_TX2_P") (class "Default")
      (node (ref "C192") (pin "1") (pinfunction "1_1") (pintype "passive"))
    )
    (net (code "20") (name "/DP1_TX3_N") (class "Default")
      (node (ref "C193") (pin "1") (pinfunction "1_1") (pintype "passive"))
    )
    (net (code "21") (name "/DP1_TX3_P") (class "Default")
      (node (ref "C194") (pin "1") (pinfunction "1_1") (pintype "passive"))
    )
    (net (code "22") (name "/DP_HPD") (class "Default")
      (node (ref "U4") (pin "26") (pinfunction "GPIO4_26") (pintype "bidirectional"))
    )
    (net (code "23") (name "/HS1_RX_N") (class "Default")
      (node (ref "U2") (pin "2") (pinfunction "CRX1N_2") (pintype "bidirectional"))
    )
    (net (code "24") (name "/HS1_RX_P") (class "Default")
      (node (ref "U2") (pin "1") (pinfunction "CRX1P_1") (pintype "bidirectional"))
    )
    (net (code "25") (name "/HS1_TX_N") (class "Default")
      (node (ref "U2") (pin "5") (pinfunction "CTX1N_5") (pintype "bidirectional"))
    )
    (net (code "26") (name "/HS1_TX_P") (class "Default")
      (node (ref "U2") (pin "4") (pinfunction "CTX1P_4") (pintype "bidirectional"))
    )
    (net (code "27") (name "/HS2_RX_N") (class "Default")
      (node (ref "U2") (pin "10") (pinfunction "CRX2N_10") (pintype "bidirectional"))
    )
    (net (code "28") (name "/HS2_RX_P") (class "Default")
      (node (ref "U2") (pin "9") (pinfunction "CRX2P_9") (pintype "bidirectional"))
    )
    (net (code "29") (name "/HS2_TX_N") (class "Default")
      (node (ref "U2") (pin "7") (pinfunction "CTX2N_7") (pintype "bidirectional"))
    )
    (net (code "30") (name "/HS2_TX_P") (class "Default")
      (node (ref "U2") (pin "6") (pinfunction "CTX2P_6") (pintype "bidirectional"))
    )
    (net (code "31") (name "/I2C_USB_IRQ_N") (class "Default")
      (node (ref "R67") (pin "2") (pinfunction "2_2") (pintype "passive"))
      (node (ref "U4") (pin "43") (pinfunction "I2C_~{IRQ1}_43") (pintype "open_collector"))
    )
    (net (code "32") (name "/I2C_USB_SCL") (class "Default")
      (node (ref "U4") (pin "47") (pinfunction "I2C_SCL1_47") (pintype "bidirectional"))
    )
    (net (code "33") (name "/I2C_USB_SDA") (class "Default")
      (node (ref "U4") (pin "46") (pinfunction "I2C_SDA1_46") (pintype "bidirectional"))
    )
    (net (code "34") (name "/SPI_CLK") (class "Default")
      (node (ref "J17") (pin "3") (pinfunction "3_3") (pintype "passive"))
      (node (ref "U3") (pin "6") (pinfunction "CLK_6") (pintype "input"))
      (node (ref "U4") (pin "37") (pinfunction "SPI_CLK_37") (pintype "output"))
    )
    (net (code "35") (name "/SPI_CS_N") (class "Default")
      (node (ref "J17") (pin "6") (pinfunction "6_6") (pintype "passive"))
      (node (ref "R44") (pin "2") (pinfunction "2_2") (pintype "passive"))
      (node (ref "U3") (pin "1") (pinfunction "CS_1") (pintype "input"))
      (node (ref "U4") (pin "39") (pinfunction "SPI_~{CS}_39") (pintype "output"))
    )
    (net (code "36") (name "/SPI_MISO") (class "Default")
      (node (ref "J17") (pin "4") (pinfunction "4_4") (pintype "passive"))
      (node (ref "R43") (pin "2") (pinfunction "2_2") (pintype "passive"))
      (node (ref "U3") (pin "2") (pinfunction "DO/IO1_2") (pintype "bidirectional"))
      (node (ref "U4") (pin "35") (pinfunction "SPI_MISO_35") (pintype "input"))
    )
    (net (code "37") (name "/SPI_MOSI") (class "Default")
      (node (ref "J17") (pin "5") (pinfunction "5_5") (pintype "passive"))
      (node (ref "U3") (pin "5") (pinfunction "DI/IO0_5") (pintype "bidirectional"))
      (node (ref "U4") (pin "36") (pinfunction "SPI_MOSI_36") (pintype "output"))
    )
    (net (code "38") (name "/SS_AM") (class "Default")
      (node (ref "Q8") (pin "1") (pinfunction "G_1") (pintype "passive"))
      (node (ref "R70") (pin "1") (pinfunction "1_1") (pintype "passive"))
      (node (ref "U2") (pin "8") (pinfunction "AMSEL_8") (pintype "input"))
      (node (ref "U4") (pin "41") (pinfunction "GPIO0_41") (pintype "bidirectional"))
    )
    (net (code "39") (name "/SS_EN") (class "Default")
      (node (ref "Q7") (pin "1") (pinfunction "G_1") (pintype "passive"))
      (node (ref "R62") (pin "1") (pinfunction "1_1") (pintype "passive"))
      (node (ref "U2") (pin "17") (pinfunction "EN_17") (pintype "input"))
      (node (ref "U4") (pin "19") (pinfunction "GPIO3_19") (pintype "bidirectional"))
    )
    (net (code "40") (name "/SS_POL") (class "Default")
      (node (ref "Q9") (pin "1") (pinfunction "G_1") (pintype "passive"))
      (node (ref "R73") (pin "1") (pinfunction "1_1") (pintype "passive"))
      (node (ref "U2") (pin "3") (pinfunction "POL_3") (pintype "input"))
      (node (ref "U4") (pin "2") (pinfunction "DEBUG1_2") (pintype "bidirectional"))
    )
    (net (code "41") (name "/SWD_CLK") (class "Default")
      (node (ref "R60") (pin "2") (pinfunction "2_2") (pintype "passive"))
      (node (ref "U4") (pin "50") (pinfunction "SWD_CLK_50") (pintype "input"))
    )
    (net (code "42") (name "/SWD_DATA") (class "Default")
      (node (ref "R59") (pin "2") (pinfunction "2_2") (pintype "passive"))
      (node (ref "U4") (pin "49") (pinfunction "SWD_DAT_49") (pintype "bidirectional"))
    )
    (net (code "43") (name "/S_SBU_N") (class "Default")
      (node (ref "R66") (pin "2") (pinfunction "2_2") (pintype "passive"))
      (node (ref "R72") (pin "1") (pinfunction "1_1") (pintype "passive"))
      (node (ref "U4") (pin "11") (pinfunction "C_SBU2_11") (pintype "bidirectional"))
    )
    (net (code "44") (name "/S_SBU_P") (class "Default")
      (node (ref "R65") (pin "2") (pinfunction "2_2") (pintype "passive"))
      (node (ref "R71") (pin "1") (pinfunction "1_1") (pintype "passive"))
      (node (ref "U4") (pin "10") (pinfunction "C_SBU1_10") (pintype "bidirectional"))
    )
    (net (code "45") (name "/USB_2P0_N") (class "Default")
      (node (ref "U4") (pin "5") (pinfunction "USB_RP_N_5") (pintype "bidirectional"))
    )
    (net (code "46") (name "/USB_2P0_P") (class "Default")
      (node (ref "U4") (pin "4") (pinfunction "USB_RP_P_4") (pintype "bidirectional"))
    )
    (net (code "47") (name "/USB_RST_IN") (class "Default")
      (node (ref "R61") (pin "1") (pinfunction "1_1") (pintype "passive"))
      (node (ref "U4") (pin "24") (pinfunction "MRESET_24") (pintype "bidirectional"))
    )
    (net (code "48") (name "/USB_RST_OUT_N") (class "Default")
      (node (ref "U4") (pin "21") (pinfunction "RESET_21") (pintype "bidirectional"))
    )
    (net (code "49") (name "/USB_VIN_REG_V3P3") (class "Default")
      (node (ref "C57") (pin "2") (pinfunction "2_2") (pintype "passive"))
      (node (ref "U4") (pin "53") (pinfunction "VIN_3V3_53") (pintype "power_in"))
    )
    (net (code "50") (name "/USB_VIN_V5P0") (class "Default")
      (node (ref "C50") (pin "2") (pinfunction "2_2") (pintype "passive"))
      (node (ref "U4") (pin "14") (pinfunction "PP_CABLE_14") (pintype "power_in"))
      (node (ref "U4") (pin "27") (pinfunction "PP_5V0_27") (pintype "power_in"))
      (node (ref "U4") (pin "28") (pinfunction "PP_5V0_28") (pintype "power_in"))
    )
    (net (code "51") (name "/X_DP1_TX0_N") (class "Default")
      (node (ref "C14") (pin "2") (pinfunction "2_2") (pintype "passive"))
      (node (ref "U2") (pin "15") (pinfunction "LNAN_15") (pintype "bidirectional"))
    )
    (net (code "52") (name "/X_DP1_TX0_P") (class "Default")
      (node (ref "C55") (pin "2") (pinfunction "2_2") (pintype "passive"))
      (node (ref "U2") (pin "16") (pinfunction "LNAP_16") (pintype "bidirectional"))
    )
    (net (code "53") (name "/X_DP1_TX1_N") (class "Default")
      (node (ref "C189") (pin "2") (pinfunction "2_2") (pintype "passive"))
      (node (ref "U2") (pin "18") (pinfunction "LNBN_18") (pintype "bidirectional"))
    )
    (net (code "54") (name "/X_DP1_TX1_P") (class "Default")
      (node (ref "C190") (pin "2") (pinfunction "2_2") (pintype "passive"))
      (node (ref "U2") (pin "19") (pinfunction "LNBP_19") (pintype "bidirectional"))
    )
    (net (code "55") (name "/X_DP1_TX2_N") (class "Default")
      (node (ref "C191") (pin "2") (pinfunction "2_2") (pintype "passive"))
      (node (ref "U2") (pin "20") (pinfunction "LNCN_20") (pintype "bidirectional"))
    )
    (net (code "56") (name "/X_DP1_TX2_P") (class "Default")
      (node (ref "C192") (pin "2") (pinfunction "2_2") (pintype "passive"))
      (node (ref "U2") (pin "21") (pinfunction "LNCP_21") (pintype "bidirectional"))
    )
    (net (code "57") (name "/X_DP1_TX3_N") (class "Default")
      (node (ref "C193") (pin "2") (pinfunction "2_2") (pintype "passive"))
      (node (ref "U2") (pin "23") (pinfunction "LNDN_23") (pintype "bidirectional"))
    )
    (net (code "58") (name "/X_DP1_TX3_P") (class "Default")
      (node (ref "C194") (pin "2") (pinfunction "2_2") (pintype "passive"))
      (node (ref "U2") (pin "24") (pinfunction "LNDP_24") (pintype "bidirectional"))
    )
    (net (code "62") (name "GND") (class "Default")
      (node (ref "C195") (pin "1") (pinfunction "1_1") (pintype "passive"))
      (node (ref "C196") (pin "1") (pinfunction "1_1") (pintype "passive"))
      (node (ref "C42") (pin "1") (pinfunction "1_1") (pintype "passive"))
      (node (ref "C43") (pin "1") (pinfunction "1_1") (pintype "passive"))
      (node (ref "C44") (pin "1") (pinfunction "1_1") (pintype "passive"))
      (node (ref "C45") (pin "1") (pinfunction "1_1") (pintype "passive"))
      (node (ref "C46") (pin "1") (pinfunction "1_1") (pintype "passive"))
      (node (ref "C47") (pin "1") (pinfunction "1_1") (pintype "passive"))
      (node (ref "C48") (pin "1") (pinfunction "1_1") (pintype "passive"))
      (node (ref "C49") (pin "1") (pinfunction "1_1") (pintype "passive"))
      (node (ref "C50") (pin "1") (pinfunction "1_1") (pintype "passive"))
      (node (ref "C51") (pin "1") (pinfunction "1_1") (pintype "passive"))
      (node (ref "C52") (pin "1") (pinfunction "1_1") (pintype "passive"))
      (node (ref "C53") (pin "1") (pinfunction "1_1") (pintype "passive"))
      (node (ref "C54") (pin "1") (pinfunction "1_1") (pintype "passive"))
      (node (ref "C57") (pin "1") (pinfunction "1_1") (pintype "passive"))
      (node (ref "J17") (pin "1") (pinfunction "1_1") (pintype "passive"))
      (node (ref "Q7") (pin "2") (pinfunction "S_2") (pintype "passive"))
      (node (ref "Q8") (pin "2") (pinfunction "S_2") (pintype "passive"))
      (node (ref "Q9") (pin "2") (pinfunction "S_2") (pintype "passive"))
      (node (ref "R222") (pin "2") (pinfunction "2_2") (pintype "passive"))
      (node (ref "R225") (pin "2") (pinfunction "2_2") (pintype "passive"))
      (node (ref "R48") (pin "1") (pinfunction "1_1") (pintype "passive"))
      (node (ref "R49") (pin "1") (pinfunction "1_1") (pintype "passive"))
      (node (ref "R51") (pin "1") (pinfunction "1_1") (pintype "passive"))
      (node (ref "R52") (pin "1") (pinfunction "1_1") (pintype "passive"))
      (node (ref "R53") (pin "1") (pinfunction "1_1") (pintype "passive"))
      (node (ref "R55") (pin "1") (pinfunction "1_1") (pintype "passive"))
      (node (ref "R60") (pin "1") (pinfunction "1_1") (pintype "passive"))
      (node (ref "R61") (pin "2") (pinfunction "2_2") (pintype "passive"))
      (node (ref "R62") (pin "2") (pinfunction "2_2") (pintype "passive"))
      (node (ref "R63") (pin "1") (pinfunction "1_1") (pintype "passive"))
      (node (ref "R64") (pin "1") (pinfunction "1_1") (pintype "passive"))
      (node (ref "R70") (pin "2") (pinfunction "2_2") (pintype "passive"))
      (node (ref "R71") (pin "2") (pinfunction "2_2") (pintype "passive"))
      (node (ref "R72") (pin "2") (pinfunction "2_2") (pintype "passive"))
      (node (ref "R73") (pin "2") (pinfunction "2_2") (pintype "passive"))
      (node (ref "U2") (pin "29") (pinfunction "PAD_29") (pintype "power_in"))
      (node (ref "U3") (pin "4") (pinfunction "GND_4") (pintype "power_in"))
      (node (ref "U4") (pin "57") (pinfunction "PAD_57") (pintype "power_in"))
    )
    (net (code "63") (name "Net-(C47-Pad2)") (class "Default")
      (node (ref "C47") (pin "2") (pinfunction "2_2") (pintype "passive"))
      (node (ref "L2") (pin "2") (pintype "passive"))
      (node (ref "U4") (pin "17") (pinfunction "VBUS_17") (pintype "power_in"))
      (node (ref "U4") (pin "18") (pinfunction "VBUS_18") (pintype "power_in"))
    )
    (net (code "64") (name "Net-(C195-Pad2)") (class "Default")
      (node (ref "C195") (pin "2") (pinfunction "2_2") (pintype "passive"))
      (node (ref "C196") (pin "2") (pinfunction "2_2") (pintype "passive"))
      (node (ref "R223") (pin "2") (pinfunction "2_2") (pintype "passive"))
      (node (ref "R224") (pin "2") (pinfunction "2_2") (pintype "passive"))
      (node (ref "R225") (pin "1") (pinfunction "1_1") (pintype "passive"))
      (node (ref "R226") (pin "1") (pinfunction "1_1") (pintype "passive"))
    )
    (net (code "65") (name "Net-(D3-K)") (class "Default")
      (node (ref "D3") (pin "3") (pinfunction "K_3") (pintype "passive"))
      (node (ref "J17") (pin "2") (pinfunction "2_2") (pintype "passive"))
    )
    (net (code "66") (name "Net-(LED1-Pad2)") (class "Default")
      (node (ref "LED1") (pin "2") (pinfunction "2_2") (pintype "passive"))
      (node (ref "R56") (pin "1") (pinfunction "1_1") (pintype "passive"))
    )
    (net (code "67") (name "Net-(LED2-Pad2)") (class "Default")
      (node (ref "LED2") (pin "2") (pinfunction "2_2") (pintype "passive"))
      (node (ref "R57") (pin "1") (pinfunction "1_1") (pintype "passive"))
    )
    (net (code "68") (name "Net-(LED3-Pad2)") (class "Default")
      (node (ref "LED3") (pin "2") (pinfunction "2_2") (pintype "passive"))
      (node (ref "R58") (pin "1") (pinfunction "1_1") (pintype "passive"))
    )
    (net (code "69") (name "Net-(Q7-D)") (class "Default")
      (node (ref "Q7") (pin "3") (pinfunction "D_3") (pintype "passive"))
      (node (ref "R56") (pin "2") (pinfunction "2_2") (pintype "passive"))
    )
    (net (code "70") (name "Net-(Q8-D)") (class "Default")
      (node (ref "Q8") (pin "3") (pinfunction "D_3") (pintype "passive"))
      (node (ref "R57") (pin "2") (pinfunction "2_2") (pintype "passive"))
    )
    (net (code "71") (name "Net-(Q9-D)") (class "Default")
      (node (ref "Q9") (pin "3") (pinfunction "D_3") (pintype "passive"))
      (node (ref "R58") (pin "2") (pinfunction "2_2") (pintype "passive"))
    )
    (net (code "72") (name "Net-(U3-~{HOLD}{slash}IO3)") (class "Default")
      (node (ref "R47") (pin "2") (pinfunction "2_2") (pintype "passive"))
      (node (ref "U3") (pin "7") (pinfunction "~{HOLD}/IO3_7") (pintype "bidirectional"))
    )
    (net (code "73") (name "Net-(U3-~{WP}{slash}IO2)") (class "Default")
      (node (ref "R45") (pin "2") (pinfunction "2_2") (pintype "passive"))
      (node (ref "U3") (pin "3") (pinfunction "~{WP}/IO2_3") (pintype "bidirectional"))
    )
    (net (code "74") (name "Net-(U4A-DEBUG_CTL1)") (class "Default")
      (node (ref "R63") (pin "2") (pinfunction "2_2") (pintype "passive"))
      (node (ref "U4") (pin "45") (pinfunction "DEBUG_CTL1_45") (pintype "bidirectional"))
    )
    (net (code "75") (name "Net-(U4A-DEBUG_CTL2)") (class "Default")
      (node (ref "R64") (pin "2") (pinfunction "2_2") (pintype "passive"))
      (node (ref "U4") (pin "44") (pinfunction "DEBUG_CTL2_44") (pintype "bidirectional"))
    )
    (net (code "76") (name "Net-(U4A-GPIO2)") (class "Default")
      (node (ref "R49") (pin "2") (pinfunction "2_2") (pintype "passive"))
      (node (ref "U4") (pin "25") (pinfunction "GPIO2_25") (pintype "bidirectional"))
    )
    (net (code "77") (name "Net-(U4A-GPIO5)") (class "Default")
      (node (ref "R51") (pin "2") (pinfunction "2_2") (pintype "passive"))
      (node (ref "U4") (pin "23") (pinfunction "GPIO5_23") (pintype "bidirectional"))
    )
    (net (code "78") (name "Net-(U4A-GPIO6)") (class "Default")
      (node (ref "R52") (pin "2") (pinfunction "2_2") (pintype "passive"))
      (node (ref "U4") (pin "20") (pinfunction "GPIO6_20") (pintype "bidirectional"))
    )
    (net (code "79") (name "Net-(U4A-GPIO7)") (class "Default")
      (node (ref "R53") (pin "2") (pinfunction "2_2") (pintype "passive"))
      (node (ref "U4") (pin "38") (pinfunction "GPIO7_38") (pintype "bidirectional"))
    )
    (net (code "80") (name "Net-(U4A-GPIO8)") (class "Default")
      (node (ref "R55") (pin "2") (pinfunction "2_2") (pintype "passive"))
      (node (ref "U4") (pin "1") (pinfunction "GPIO8_1") (pintype "bidirectional"))
    )
    (net (code "81") (name "Net-(U4A-RPD_G1)") (class "Default")
      (node (ref "R50") (pin "1") (pinfunction "1_1") (pintype "passive"))
      (node (ref "U4") (pin "12") (pinfunction "RPD_G1_12") (pintype "bidirectional"))
    )
    (net (code "82") (name "Net-(U4A-RPD_G2)") (class "Default")
      (node (ref "R54") (pin "1") (pinfunction "1_1") (pintype "passive"))
      (node (ref "U4") (pin "16") (pinfunction "RPD_G2_16") (pintype "bidirectional"))
    )
    (net (code "83") (name "Net-(U4A-R_OSC)") (class "Default")
      (node (ref "R48") (pin "2") (pinfunction "2_2") (pintype "passive"))
      (node (ref "U4") (pin "52") (pinfunction "R_OSC_52") (pintype "bidirectional"))
    )
    (net (code "84") (name "Net-(U4A-SS)") (class "Default")
      (node (ref "C46") (pin "2") (pinfunction "2_2") (pintype "passive"))
      (node (ref "U4") (pin "3") (pinfunction "SS_3") (pintype "input"))
    )
    (net (code "85") (name "Net-(U4B-BUSPOWER)") (class "Default")
      (node (ref "R221") (pin "1") (pinfunction "1_1") (pintype "passive"))
      (node (ref "R222") (pin "1") (pinfunction "1_1") (pintype "passive"))
      (node (ref "U4") (pin "22") (pinfunction "BUSPOWER_22") (pintype "power_in"))
    )
    (net (code "86") (name "Net-(U4B-LDO_1V8A)") (class "Default")
      (node (ref "C54") (pin "2") (pinfunction "2_2") (pintype "passive"))
      (node (ref "U4") (pin "56") (pinfunction "LDO_1V8A_56") (pintype "power_in"))
    )
    (net (code "87") (name "Net-(U4B-LDO_1V8D)") (class "Default")
      (node (ref "C53") (pin "2") (pinfunction "2_2") (pintype "passive"))
      (node (ref "U4") (pin "40") (pinfunction "LDO_1V8D_40") (pintype "power_in"))
    )
    (net (code "88") (name "Net-(U4B-LDO_BMC)") (class "Default")
      (node (ref "C51") (pin "2") (pinfunction "2_2") (pintype "passive"))
      (node (ref "U4") (pin "48") (pinfunction "LDO_BMC_48") (pintype "power_in"))
    )
    (net (code "89") (name "USB_3V3") (class "Default")
      (node (ref "C42") (pin "2") (pinfunction "2_2") (pintype "passive"))
      (node (ref "C43") (pin "2") (pinfunction "2_2") (pintype "passive"))
      (node (ref "C52") (pin "2") (pinfunction "2_2") (pintype "passive"))
      (node (ref "D3") (pin "1") (pinfunction "A_1") (pintype "passive"))
      (node (ref "LED1") (pin "1") (pinfunction "1_1") (pintype "passive"))
      (node (ref "LED2") (pin "1") (pinfunction "1_1") (pintype "passive"))
      (node (ref "LED3") (pin "1") (pinfunction "1_1") (pintype "passive"))
      (node (ref "R221") (pin "2") (pinfunction "2_2") (pintype "passive"))
      (node (ref "R223") (pin "1") (pinfunction "1_1") (pintype "passive"))
      (node (ref "R43") (pin "1") (pinfunction "1_1") (pintype "passive"))
      (node (ref "R44") (pin "1") (pinfunction "1_1") (pintype "passive"))
      (node (ref "R45") (pin "1") (pinfunction "1_1") (pintype "passive"))
      (node (ref "R47") (pin "1") (pinfunction "1_1") (pintype "passive"))
      (node (ref "R59") (pin "1") (pinfunction "1_1") (pintype "passive"))
      (node (ref "R65") (pin "1") (pinfunction "1_1") (pintype "passive"))
      (node (ref "R66") (pin "1") (pinfunction "1_1") (pintype "passive"))
      (node (ref "R67") (pin "1") (pinfunction "1_1") (pintype "passive"))
      (node (ref "U2") (pin "22") (pinfunction "VCC_22") (pintype "power_in"))
      (node (ref "U3") (pin "8") (pinfunction "VCC_8") (pintype "power_in"))
      (node (ref "U4") (pin "42") (pinfunction "VDDIO_42") (pintype "power_in"))
      (node (ref "U4") (pin "51") (pinfunction "LDO_3V3_51") (pintype "power_in"))
    )
    (net (code "90") (name "VBAT") (class "Default")
      (node (ref "C48") (pin "2") (pinfunction "2_2") (pintype "passive"))
      (node (ref "C49") (pin "2") (pinfunction "2_2") (pintype "passive"))
      (node (ref "U4") (pin "33") (pinfunction "PP_HV_33") (pintype "power_in"))
      (node (ref "U4") (pin "34") (pinfunction "PP_HV_34") (pintype "power_in"))
    )
    (net (code "91") (name "VBUS") (class "Default") (node (ref "L2") (pin "1") (pintype "passive")))
    (net (code "92") (name "unconnected-(U2-CSBU1-Pad11)") (class "Default")
      (node (ref "U2") (pin "11") (pinfunction "CSBU1_11") (pintype "bidirectional+no_connect"))
    )
    (net (code "93") (name "unconnected-(U2-CSBU2-Pad12)") (class "Default")
      (node (ref "U2") (pin "12") (pinfunction "CSBU2_12") (pintype "bidirectional+no_connect"))
    )
    (net (code "94") (name "unconnected-(U2-SBU1-Pad13)") (class "Default")
      (node (ref "U2") (pin "13") (pinfunction "SBU1_13") (pintype "bidirectional+no_connect"))
    )
    (net (code "95") (name "unconnected-(U2-SBU2-Pad14)") (class "Default")
      (node (ref "U2") (pin "14") (pinfunction "SBU2_14") (pintype "bidirectional+no_connect"))
    )
    (net (code "96") (name "unconnected-(U2-SSRXN-Pad27)") (class "Default")
      (node (ref "U2") (pin "27") (pinfunction "SSRXN_27") (pintype "bidirectional+no_connect"))
    )
    (net (code "97") (name "unconnected-(U2-SSRXP-Pad28)") (class "Default")
      (node (ref "U2") (pin "28") (pinfunction "SSRXP_28") (pintype "bidirectional+no_connect"))
    )
    (net (code "98") (name "unconnected-(U2-SSTXN-Pad25)") (class "Default")
      (node (ref "U2") (pin "25") (pinfunction "SSTXN_25") (pintype "bidirectional+no_connect"))
    )
    (net (code "99") (name "unconnected-(U2-SSTXP-Pad26)") (class "Default")
      (node (ref "U2") (pin "26") (pinfunction "SSTXP_26") (pintype "bidirectional+no_connect"))
    )
    (net (code "100") (name "unconnected-(U4A-HV_GATE1-Pad31)") (class "Default")
      (node (ref "U4") (pin "31") (pinfunction "HV_GATE1_31") (pintype "output"))
    )
    (net (code "101") (name "unconnected-(U4A-HV_GATE2-Pad32)") (class "Default")
      (node (ref "U4") (pin "32") (pinfunction "HV_GATE2_32") (pintype "output"))
    )
    (net (code "102") (name "unconnected-(U4A-SENSEN-Pad29)") (class "Default")
      (node (ref "U4") (pin "29") (pinfunction "SENSEN_29") (pintype "input"))
    )
    (net (code "103") (name "unconnected-(U4A-SENSEP-Pad30)") (class "Default")
      (node (ref "U4") (pin "30") (pinfunction "SENSEP_30") (pintype "input"))
    )
  )
)
